# sensortester.net
KiCad netlist of a schematic drawn in EAGLE
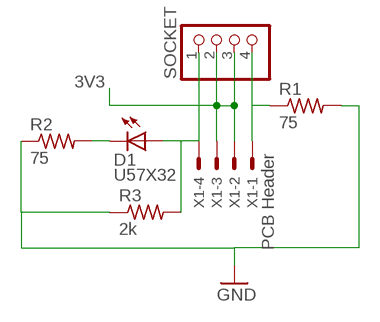
[diagram p0: schematic, sheet 1]

(export (version "E")
  (design (tool "Eeschema 10.0.6"))
  (components
    (comp (ref "D1")
      (value "U57X32")
      (footprint "eagle-import:U57X32")
      (libsource (lib "eagle-import") (part "U57X32"))
    )
    (comp (ref "R1")
      (value "75")
      (footprint "eagle-import:0204_5")
      (libsource (lib "eagle-import") (part "R-US_0204/5"))
    )
    (comp (ref "R2")
      (value "75")
      (footprint "eagle-import:0204_5")
      (libsource (lib "eagle-import") (part "R-US_0204/5"))
    )
    (comp (ref "R3")
      (value "2k")
      (footprint "eagle-import:0204_5")
      (libsource (lib "eagle-import") (part "R-US_0204/5"))
    )
    (comp (ref "SOCKET")
      (value "PINHD-1X4")
      (footprint "eagle-import:1X04")
      (libsource (lib "eagle-import") (part "PINHD-1X4"))
    )
    (comp (ref "X1")
      (value "PCB Header")
      (footprint "eagle-import:22-23-2041")
      (fields (field (name "MF") "MOLEX") (field (name "MPN") "22-23-2041"))
      (libsource (lib "eagle-import") (part "22-23-2041"))
    )
  )
  (nets
    (net (code "1") (name "/3V3") (class "Default")
      (node (ref "SOCKET") (pin "2") (pinfunction "2_2") (pintype "passive"))
      (node (ref "SOCKET") (pin "3") (pinfunction "3_3") (pintype "passive"))
      (node (ref "X1") (pin "2") (pinfunction "S_2") (pintype "passive"))
      (node (ref "X1") (pin "3") (pinfunction "S_3") (pintype "passive"))
    )
    (net (code "2") (name "GND") (class "Default")
      (node (ref "R1") (pin "2") (pinfunction "2_2") (pintype "passive"))
      (node (ref "R2") (pin "1") (pinfunction "1_1") (pintype "passive"))
      (node (ref "R3") (pin "1") (pinfunction "1_1") (pintype "passive"))
    )
    (net (code "3") (name "Net-(D1-C)") (class "Default")
      (node (ref "D1") (pin "K") (pinfunction "C_K") (pintype "passive"))
      (node (ref "R2") (pin "2") (pinfunction "2_2") (pintype "passive"))
    )
    (net (code "4") (name "Net-(X1A-S)") (class "Default")
      (node (ref "R1") (pin "1") (pinfunction "1_1") (pintype "passive"))
      (node (ref "SOCKET") (pin "4") (pinfunction "4_4") (pintype "passive"))
      (node (ref "X1") (pin "1") (pinfunction "S_1") (pintype "passive"))
    )
    (net (code "5") (name "Net-(X1D-S)") (class "Default")
      (node (ref "D1") (pin "A") (pinfunction "A_A") (pintype "passive"))
      (node (ref "R3") (pin "2") (pinfunction "2_2") (pintype "passive"))
      (node (ref "SOCKET") (pin "1") (pinfunction "1_1") (pintype "passive"))
      (node (ref "X1") (pin "4") (pinfunction "S_4") (pintype "passive"))
    )
  )
)
